# Connectors.net
KiCad netlist of a schematic drawn in Altium Designer
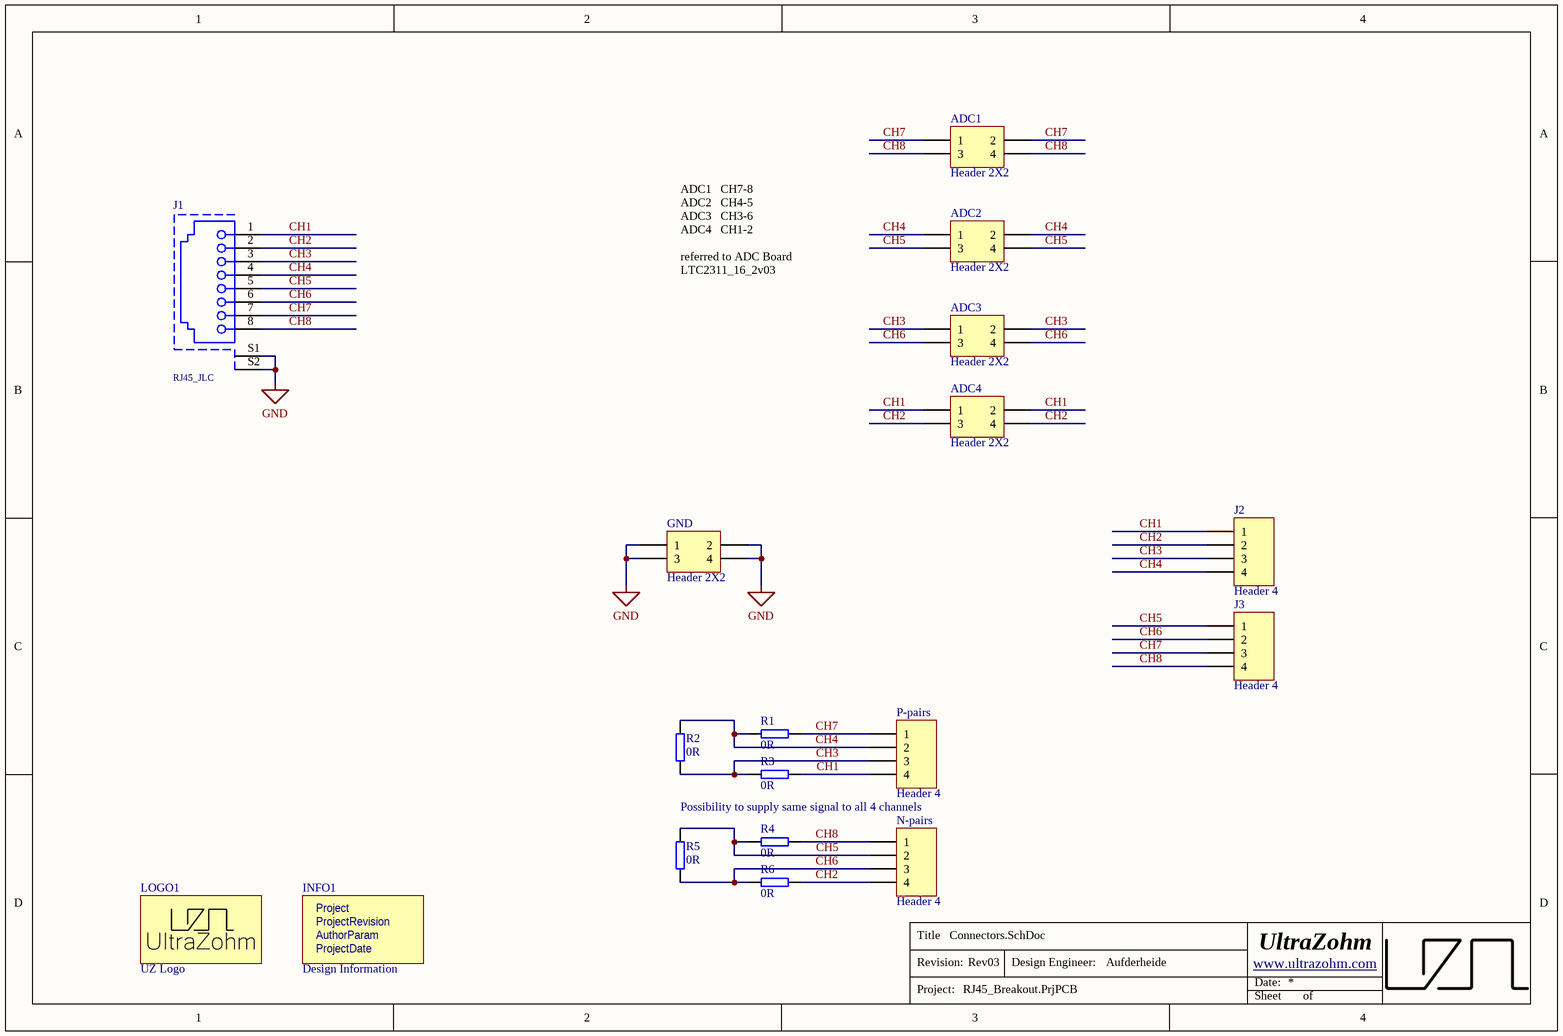
[diagram p0: Connectors.SchDoc]

(export (version "E")
  (design (tool "Eeschema 10.0.6"))
  (components
    (comp (ref "ADC1")
      (value "Header 2X2")
      (footprint "HDR2X2")
      (description "Header, 2-Pin, Dual row")
      (fields (field (name "LCSC PART #") "C160338") (field (name "PUBLISHER") "Altium Limited"))
      (libsource (lib "Miscellaneous Connectors") (part "Header 2X2"))
    )
    (comp (ref "ADC2")
      (value "Header 2X2")
      (footprint "HDR2X2")
      (description "Header, 2-Pin, Dual row")
      (fields (field (name "LCSC PART #") "C160338") (field (name "PUBLISHER") "Altium Limited"))
      (libsource (lib "Miscellaneous Connectors") (part "Header 2X2"))
    )
    (comp (ref "ADC3")
      (value "Header 2X2")
      (footprint "HDR2X2")
      (description "Header, 2-Pin, Dual row")
      (fields (field (name "LCSC PART #") "C160338") (field (name "PUBLISHER") "Altium Limited"))
      (libsource (lib "Miscellaneous Connectors") (part "Header 2X2"))
    )
    (comp (ref "ADC4")
      (value "Header 2X2")
      (footprint "HDR2X2")
      (description "Header, 2-Pin, Dual row")
      (fields (field (name "LCSC PART #") "C160338") (field (name "PUBLISHER") "Altium Limited"))
      (libsource (lib "Miscellaneous Connectors") (part "Header 2X2"))
    )
    (comp (ref "GND")
      (value "Header 2X2")
      (footprint "HDR2X2")
      (description "Header, 2-Pin, Dual row")
      (fields (field (name "LCSC PART #") "C160338") (field (name "PUBLISHER") "Altium Limited"))
      (libsource (lib "Miscellaneous Connectors") (part "Header 2X2"))
    )
    (comp (ref "INFO1")
      (value "Design Information")
      (footprint "Design_info")
      (fields (field (name "MANUFACTURER") "UltraZohm") (field (name "CREATED FROM") "MGremer"))
      (libsource (lib "user") (part "Design_info"))
    )
    (comp (ref "J1")
      (value "RJ45_JLC")
      (footprint "RJ45_JLC")
      (description "Modular Jack WR-MJ, Tab Down, Shielded, Horizontal Entry, THT, 8P8C")
      (fields
        (field (name "PART NUMBER") "61500814221")
        (field (name "LCSC PART #") "C386758")
        (field (name "PUBLISHER") "Wurth Elektronik")
      )
      (libsource (lib "RJ45_Breakout") (part "RJ45_JLC"))
    )
    (comp (ref "J2")
      (value "Header 4")
      (footprint "HDR1X4")
      (description "Header, 4-Pin")
      (fields (field (name "LCSC PART #") "C124378") (field (name "PUBLISHER") "Altium Limited"))
      (libsource (lib "Miscellaneous Connectors") (part "Header 4"))
    )
    (comp (ref "J3")
      (value "Header 4")
      (footprint "HDR1X4")
      (description "Header, 4-Pin")
      (fields (field (name "LCSC PART #") "C124378") (field (name "PUBLISHER") "Altium Limited"))
      (libsource (lib "Miscellaneous Connectors") (part "Header 4"))
    )
    (comp (ref "LOGO1")
      (value "UZ Logo")
      (footprint "UZ_Logo_small")
      (fields
        (field (name "MANUFACTURER PART NUMBER") "Logo small")
        (field (name "MANUFACTURER") "UltraZohm")
        (field (name "CREATED") "Jan2021_Liegmann")
        (field (name "CREATED FROM") "MGremer")
      )
      (libsource (lib "user") (part "UZ Logo"))
    )
    (comp (ref "N-pairs")
      (value "Header 4")
      (footprint "HDR1X4")
      (description "Header, 4-Pin")
      (fields (field (name "LCSC PART #") "C124378") (field (name "PUBLISHER") "Altium Limited"))
      (libsource (lib "Miscellaneous Connectors") (part "Header 4"))
    )
    (comp (ref "P-pairs")
      (value "Header 4")
      (footprint "HDR1X4")
      (description "Header, 4-Pin")
      (fields (field (name "LCSC PART #") "C124378") (field (name "PUBLISHER") "Altium Limited"))
      (libsource (lib "Miscellaneous Connectors") (part "Header 4"))
    )
    (comp (ref "R1")
      (value "0R")
      (footprint "RES 0603_1608")
      (description "SMD resistor E24 series")
      (fields
        (field (name "MANUFACTURER PART NUMBER") "RC0603JR-070RL")
        (field (name "MANUFACTURER") "YAGEO")
        (field (name "CREATED FROM") "MGremer")
      )
      (libsource (lib "user") (part "Resistor"))
    )
    (comp (ref "R2")
      (value "0R")
      (footprint "RES 0603_1608")
      (description "SMD resistor E24 series")
      (fields
        (field (name "MANUFACTURER PART NUMBER") "RC0603JR-070RL")
        (field (name "MANUFACTURER") "YAGEO")
        (field (name "CREATED FROM") "MGremer")
      )
      (libsource (lib "user") (part "Resistor"))
    )
    (comp (ref "R3")
      (value "0R")
      (footprint "RES 0603_1608")
      (description "SMD resistor E24 series")
      (fields
        (field (name "MANUFACTURER PART NUMBER") "RC0603JR-070RL")
        (field (name "MANUFACTURER") "YAGEO")
        (field (name "CREATED FROM") "MGremer")
      )
      (libsource (lib "user") (part "Resistor"))
    )
    (comp (ref "R4")
      (value "0R")
      (footprint "RES 0603_1608")
      (description "SMD resistor E24 series")
      (fields
        (field (name "MANUFACTURER PART NUMBER") "RC0603JR-070RL")
        (field (name "MANUFACTURER") "YAGEO")
        (field (name "CREATED FROM") "MGremer")
      )
      (libsource (lib "user") (part "Resistor"))
    )
    (comp (ref "R5")
      (value "0R")
      (footprint "RES 0603_1608")
      (description "SMD resistor E24 series")
      (fields
        (field (name "MANUFACTURER PART NUMBER") "RC0603JR-070RL")
        (field (name "MANUFACTURER") "YAGEO")
        (field (name "CREATED FROM") "MGremer")
      )
      (libsource (lib "user") (part "Resistor"))
    )
    (comp (ref "R6")
      (value "0R")
      (footprint "RES 0603_1608")
      (description "SMD resistor E24 series")
      (fields
        (field (name "MANUFACTURER PART NUMBER") "RC0603JR-070RL")
        (field (name "MANUFACTURER") "YAGEO")
        (field (name "CREATED FROM") "MGremer")
      )
      (libsource (lib "user") (part "Resistor"))
    )
  )
  (nets
    (net (code "1") (name "/CH1") (class "Default")
      (node (ref "ADC4") (pin "1") (pinfunction "1_1") (pintype "passive"))
      (node (ref "ADC4") (pin "2") (pinfunction "2_2") (pintype "passive"))
      (node (ref "J1") (pin "1") (pinfunction "1_1") (pintype "passive"))
      (node (ref "J2") (pin "1") (pinfunction "1_1") (pintype "passive"))
      (node (ref "P-pairs") (pin "4") (pinfunction "4_4") (pintype "passive"))
      (node (ref "R3") (pin "1") (pinfunction "1_1") (pintype "passive"))
    )
    (net (code "2") (name "/CH2") (class "Default")
      (node (ref "ADC4") (pin "3") (pinfunction "3_3") (pintype "passive"))
      (node (ref "ADC4") (pin "4") (pinfunction "4_4") (pintype "passive"))
      (node (ref "J1") (pin "2") (pinfunction "2_2") (pintype "passive"))
      (node (ref "J2") (pin "2") (pinfunction "2_2") (pintype "passive"))
      (node (ref "N-pairs") (pin "4") (pinfunction "4_4") (pintype "passive"))
      (node (ref "R6") (pin "1") (pinfunction "1_1") (pintype "passive"))
    )
    (net (code "3") (name "/CH3") (class "Default")
      (node (ref "ADC3") (pin "1") (pinfunction "1_1") (pintype "passive"))
      (node (ref "ADC3") (pin "2") (pinfunction "2_2") (pintype "passive"))
      (node (ref "J1") (pin "3") (pinfunction "3_3") (pintype "passive"))
      (node (ref "J2") (pin "3") (pinfunction "3_3") (pintype "passive"))
      (node (ref "P-pairs") (pin "3") (pinfunction "3_3") (pintype "passive"))
      (node (ref "R2") (pin "1") (pinfunction "1_1") (pintype "passive"))
      (node (ref "R3") (pin "2") (pinfunction "2_2") (pintype "passive"))
    )
    (net (code "4") (name "/CH4") (class "Default")
      (node (ref "ADC2") (pin "1") (pinfunction "1_1") (pintype "passive"))
      (node (ref "ADC2") (pin "2") (pinfunction "2_2") (pintype "passive"))
      (node (ref "J1") (pin "4") (pinfunction "4_4") (pintype "passive"))
      (node (ref "J2") (pin "4") (pinfunction "4_4") (pintype "passive"))
      (node (ref "P-pairs") (pin "2") (pinfunction "2_2") (pintype "passive"))
      (node (ref "R1") (pin "2") (pinfunction "2_2") (pintype "passive"))
      (node (ref "R2") (pin "2") (pinfunction "2_2") (pintype "passive"))
    )
    (net (code "5") (name "/CH5") (class "Default")
      (node (ref "ADC2") (pin "3") (pinfunction "3_3") (pintype "passive"))
      (node (ref "ADC2") (pin "4") (pinfunction "4_4") (pintype "passive"))
      (node (ref "J1") (pin "5") (pinfunction "5_5") (pintype "passive"))
      (node (ref "J3") (pin "1") (pinfunction "1_1") (pintype "passive"))
      (node (ref "N-pairs") (pin "2") (pinfunction "2_2") (pintype "passive"))
      (node (ref "R4") (pin "2") (pinfunction "2_2") (pintype "passive"))
      (node (ref "R5") (pin "2") (pinfunction "2_2") (pintype "passive"))
    )
    (net (code "6") (name "/CH6") (class "Default")
      (node (ref "ADC3") (pin "3") (pinfunction "3_3") (pintype "passive"))
      (node (ref "ADC3") (pin "4") (pinfunction "4_4") (pintype "passive"))
      (node (ref "J1") (pin "6") (pinfunction "6_6") (pintype "passive"))
      (node (ref "J3") (pin "2") (pinfunction "2_2") (pintype "passive"))
      (node (ref "N-pairs") (pin "3") (pinfunction "3_3") (pintype "passive"))
      (node (ref "R5") (pin "1") (pinfunction "1_1") (pintype "passive"))
      (node (ref "R6") (pin "2") (pinfunction "2_2") (pintype "passive"))
    )
    (net (code "7") (name "/CH7") (class "Default")
      (node (ref "ADC1") (pin "1") (pinfunction "1_1") (pintype "passive"))
      (node (ref "ADC1") (pin "2") (pinfunction "2_2") (pintype "passive"))
      (node (ref "J1") (pin "7") (pinfunction "7_7") (pintype "passive"))
      (node (ref "J3") (pin "3") (pinfunction "3_3") (pintype "passive"))
      (node (ref "P-pairs") (pin "1") (pinfunction "1_1") (pintype "passive"))
      (node (ref "R1") (pin "1") (pinfunction "1_1") (pintype "passive"))
    )
    (net (code "8") (name "/CH8") (class "Default")
      (node (ref "ADC1") (pin "3") (pinfunction "3_3") (pintype "passive"))
      (node (ref "ADC1") (pin "4") (pinfunction "4_4") (pintype "passive"))
      (node (ref "J1") (pin "8") (pinfunction "8_8") (pintype "passive"))
      (node (ref "J3") (pin "4") (pinfunction "4_4") (pintype "passive"))
      (node (ref "N-pairs") (pin "1") (pinfunction "1_1") (pintype "passive"))
      (node (ref "R4") (pin "1") (pinfunction "1_1") (pintype "passive"))
    )
    (net (code "9") (name "GND") (class "Default")
      (node (ref "GND") (pin "1") (pinfunction "1_1") (pintype "passive"))
      (node (ref "GND") (pin "2") (pinfunction "2_2") (pintype "passive"))
      (node (ref "GND") (pin "3") (pinfunction "3_3") (pintype "passive"))
      (node (ref "GND") (pin "4") (pinfunction "4_4") (pintype "passive"))
      (node (ref "J1") (pin "S1") (pinfunction "S1_S1") (pintype "passive"))
      (node (ref "J1") (pin "S2") (pinfunction "S2_S2") (pintype "passive"))
    )
  )
)
